# POWER.net
KiCad netlist of a schematic drawn in Altium Designer
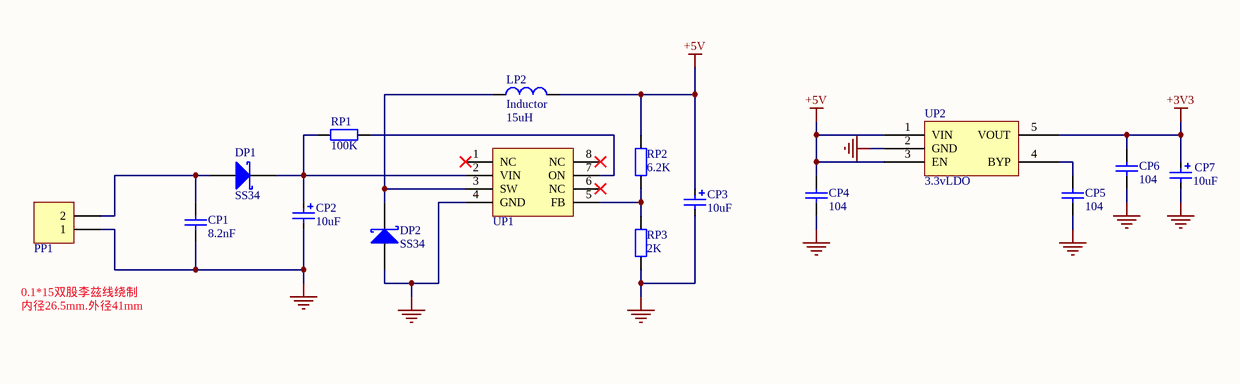
[diagram p0: POWER.SchDoc]

(export (version "E")
  (design (tool "Eeschema 10.0.6"))
  (components
    (comp (ref "CP1")
      (value "8.2nF")
      (footprint "CAPC2012N")
      (description "Capacitor")
      (fields (field (name "Comment") "Cap1") (field (name "PUBLISHER") "Altium Limited"))
      (libsource (lib "Peace的集成库") (part "Cap1"))
    )
    (comp (ref "CP2")
      (value "10uF")
      (footprint "CAP_TAN_B1210")
      (description "Capacitor")
      (fields (field (name "Comment") "Cap_Tan"))
      (libsource (lib "Peace的集成库") (part "Cap_Tan"))
    )
    (comp (ref "CP3")
      (value "10uF")
      (footprint "CAP_TAN_B1210")
      (description "Capacitor")
      (fields (field (name "Comment") "Cap_Tan"))
      (libsource (lib "Peace的集成库") (part "Cap_Tan"))
    )
    (comp (ref "CP4")
      (value "104")
      (footprint "CAPC1608N")
      (description "Capacitor")
      (fields (field (name "Comment") "Cap1") (field (name "PUBLISHER") "Altium Limited"))
      (libsource (lib "Peace的集成库") (part "Cap1"))
    )
    (comp (ref "CP5")
      (value "104")
      (footprint "CAPC1608N")
      (description "Capacitor")
      (fields (field (name "Comment") "Cap1") (field (name "PUBLISHER") "Altium Limited"))
      (libsource (lib "Peace的集成库") (part "Cap1"))
    )
    (comp (ref "CP6")
      (value "104")
      (footprint "CAPC1608N")
      (description "Capacitor")
      (fields (field (name "Comment") "Cap1") (field (name "PUBLISHER") "Altium Limited"))
      (libsource (lib "Peace的集成库") (part "Cap1"))
    )
    (comp (ref "CP7")
      (value "10uF")
      (footprint "CAP_TAN_P0805")
      (description "Capacitor")
      (fields (field (name "Comment") "Cap_Tan"))
      (libsource (lib "Peace的集成库") (part "Cap_Tan"))
    )
    (comp (ref "DP1")
      (value "SS34")
      (footprint "DO-214AC")
      (description "Schottky Diode")
      (fields (field (name "PUBLISHER") "Altium Limited"))
      (libsource (lib "Peace的集成库") (part "D Schottky"))
    )
    (comp (ref "DP2")
      (value "SS34")
      (footprint "DO-214AC")
      (description "Schottky Diode")
      (fields (field (name "PUBLISHER") "Altium Limited"))
      (libsource (lib "Peace的集成库") (part "D Schottky"))
    )
    (comp (ref "LP2")
      (value "Inductor")
      (footprint "IND_7032")
      (fields (field (name "ALTIUM_VALUE") "15uH") (field (name "PUBLISHER") "Altium Limited"))
      (libsource (lib "原理图库") (part "Inductor"))
    )
    (comp (ref "PP1")
      (value "Header 2")
      (footprint "HDR1X2")
      (description "Header, 2-Pin")
      (fields (field (name "PUBLISHER") "Altium Limited"))
      (libsource (lib "Peace的集成库") (part "Header 2"))
    )
    (comp (ref "RP1")
      (value "100K")
      (footprint "RESC1608N")
      (description "Resistor")
      (fields (field (name "Comment") "Res1") (field (name "PUBLISHER") "Altium Limited"))
      (libsource (lib "") (part "Res1_1"))
    )
    (comp (ref "RP2")
      (value "6.2K")
      (footprint "RESC1608N")
      (description "Resistor")
      (fields (field (name "Comment") "Res1") (field (name "PUBLISHER") "Altium Limited"))
      (libsource (lib "Peace的集成库") (part "Res1"))
    )
    (comp (ref "RP3")
      (value "2K")
      (footprint "RESC1608N")
      (description "Resistor")
      (fields (field (name "Comment") "Res1") (field (name "PUBLISHER") "Altium Limited"))
      (libsource (lib "Peace的集成库") (part "Res1"))
    )
    (comp (ref "UP1") (value "XKT-3168") (footprint "SOP8_L") (libsource (lib "Peace的集成库") (part "XKT-3168")))
    (comp (ref "UP2")
      (value "3.3vLDO")
      (footprint "SOT23-5_L")
      (libsource (lib "Peace的集成库") (part "LDO-SOT23-5"))
    )
  )
  (nets
    (net (code "1") (name "+3V3") (class "Default")
      (node (ref "CP6") (pin "2") (pinfunction "2_2") (pintype "passive"))
      (node (ref "CP7") (pin "1") (pinfunction "1_1") (pintype "passive"))
      (node (ref "UP2") (pin "5") (pinfunction "VOUT_5") (pintype "passive"))
    )
    (net (code "2") (name "+5V") (class "Default")
      (node (ref "CP3") (pin "1") (pinfunction "1_1") (pintype "passive"))
      (node (ref "CP4") (pin "2") (pinfunction "2_2") (pintype "passive"))
      (node (ref "LP2") (pin "2") (pinfunction "2_2") (pintype "passive"))
      (node (ref "RP2") (pin "2") (pinfunction "2_2") (pintype "passive"))
      (node (ref "UP2") (pin "1") (pinfunction "VIN_1") (pintype "passive"))
      (node (ref "UP2") (pin "3") (pinfunction "EN_3") (pintype "passive"))
    )
    (net (code "3") (name "GND") (class "Default")
      (node (ref "CP1") (pin "1") (pinfunction "1_1") (pintype "passive"))
      (node (ref "CP2") (pin "2") (pinfunction "2_2") (pintype "passive"))
      (node (ref "CP3") (pin "2") (pinfunction "2_2") (pintype "passive"))
      (node (ref "CP4") (pin "1") (pinfunction "1_1") (pintype "passive"))
      (node (ref "CP5") (pin "1") (pinfunction "1_1") (pintype "passive"))
      (node (ref "CP6") (pin "1") (pinfunction "1_1") (pintype "passive"))
      (node (ref "CP7") (pin "2") (pinfunction "2_2") (pintype "passive"))
      (node (ref "DP2") (pin "1") (pinfunction "A_1") (pintype "passive"))
      (node (ref "PP1") (pin "1") (pinfunction "1_1") (pintype "passive"))
      (node (ref "RP3") (pin "1") (pinfunction "1_1") (pintype "passive"))
      (node (ref "UP1") (pin "4") (pinfunction "GND_4") (pintype "passive"))
      (node (ref "UP2") (pin "2") (pinfunction "GND_2") (pintype "passive"))
    )
    (net (code "4") (name "Net-(DP1-A)") (class "Default")
      (node (ref "CP1") (pin "2") (pinfunction "2_2") (pintype "passive"))
      (node (ref "DP1") (pin "1") (pinfunction "A_1") (pintype "passive"))
      (node (ref "PP1") (pin "2") (pinfunction "2_2") (pintype "passive"))
    )
    (net (code "5") (name "Net-(DP1-K)") (class "Default")
      (node (ref "CP2") (pin "1") (pinfunction "1_1") (pintype "passive"))
      (node (ref "DP1") (pin "2") (pinfunction "K_2") (pintype "passive"))
      (node (ref "RP1") (pin "1") (pinfunction "1_1") (pintype "passive"))
      (node (ref "UP1") (pin "2") (pinfunction "VIN_2") (pintype "passive"))
    )
    (net (code "6") (name "Net-(DP2-K)") (class "Default")
      (node (ref "DP2") (pin "2") (pinfunction "K_2") (pintype "passive"))
      (node (ref "LP2") (pin "1") (pinfunction "1_1") (pintype "passive"))
      (node (ref "UP1") (pin "3") (pinfunction "SW_3") (pintype "passive"))
    )
    (net (code "7") (name "Net-(UP1-FB)") (class "Default")
      (node (ref "RP2") (pin "1") (pinfunction "1_1") (pintype "passive"))
      (node (ref "RP3") (pin "2") (pinfunction "2_2") (pintype "passive"))
      (node (ref "UP1") (pin "5") (pinfunction "FB_5") (pintype "passive"))
    )
    (net (code "8") (name "Net-(UP1-ON)") (class "Default")
      (node (ref "RP1") (pin "2") (pinfunction "2_2") (pintype "passive"))
      (node (ref "UP1") (pin "7") (pinfunction "ON_7") (pintype "passive"))
    )
    (net (code "9") (name "Net-(UP2-BYP)") (class "Default")
      (node (ref "CP5") (pin "2") (pinfunction "2_2") (pintype "passive"))
      (node (ref "UP2") (pin "4") (pinfunction "BYP_4") (pintype "passive"))
    )
    (net (code "10") (name "unconnected-(UP1-NC-Pad1)") (class "Default")
      (node (ref "UP1") (pin "1") (pinfunction "NC_1") (pintype "passive+no_connect"))
    )
    (net (code "11") (name "unconnected-(UP1-NC-Pad6)") (class "Default")
      (node (ref "UP1") (pin "6") (pinfunction "NC_6") (pintype "passive+no_connect"))
    )
    (net (code "12") (name "unconnected-(UP1-NC-Pad8)") (class "Default")
      (node (ref "UP1") (pin "8") (pinfunction "NC_8") (pintype "passive+no_connect"))
    )
  )
)
